# schematics.net
KiCad netlist of a schematic drawn in EAGLE
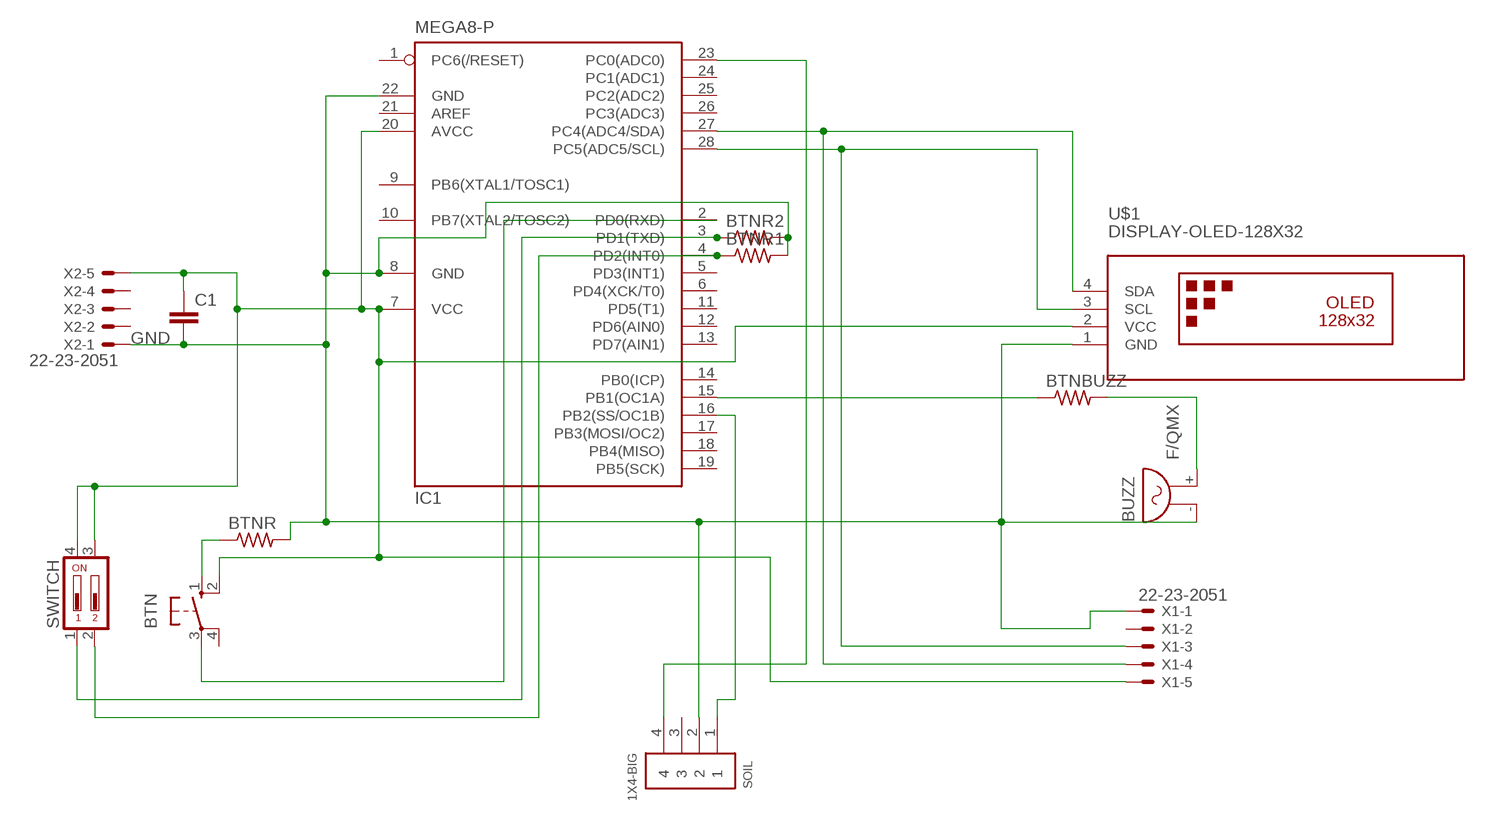
[diagram p0: schematic, sheet 1]

(export (version "E")
  (design (tool "Eeschema 10.0.6"))
  (components
    (comp (ref "BTN")
      (value "10-XX")
      (footprint "eagle-import:B3F-10XX")
      (fields (field (name "MPN") "B3F-1000"))
      (libsource (lib "eagle-import") (part "10-XX"))
    )
    (comp (ref "BTNBUZZ")
      (value "R-US_0204/7")
      (footprint "eagle-import:0204_7")
      (libsource (lib "eagle-import") (part "R-US_0204/7"))
    )
    (comp (ref "BTNR")
      (value "R-US_0204/7")
      (footprint "eagle-import:0204_7")
      (libsource (lib "eagle-import") (part "R-US_0204/7"))
    )
    (comp (ref "BTNR1")
      (value "R-US_0204/7")
      (footprint "eagle-import:0204_7")
      (libsource (lib "eagle-import") (part "R-US_0204/7"))
    )
    (comp (ref "BTNR2")
      (value "R-US_0204/7")
      (footprint "eagle-import:0204_7")
      (libsource (lib "eagle-import") (part "R-US_0204/7"))
    )
    (comp (ref "BUZZ")
      (value "F/QMX")
      (footprint "eagle-import:F_QMX")
      (libsource (lib "eagle-import") (part "F/QMX"))
    )
    (comp (ref "C1")
      (value "C-EU025-025X050")
      (footprint "eagle-import:C025-025X050")
      (libsource (lib "eagle-import") (part "C-EU025-025X050"))
    )
    (comp (ref "IC1")
      (value "MEGA8-P")
      (footprint "eagle-import:DIL28-3")
      (libsource (lib "eagle-import") (part "MEGA8-P"))
    )
    (comp (ref "SOIL")
      (value "1X4-BIG")
      (footprint "eagle-import:1X04-BIG")
      (libsource (lib "eagle-import") (part "1X4-BIG"))
    )
    (comp (ref "SWITCH")
      (value "DIP02YL")
      (footprint "eagle-import:DIP02YL")
      (libsource (lib "eagle-import") (part "DIP02YL"))
    )
    (comp (ref "U$1")
      (value "DISPLAY-OLED-128X32")
      (footprint "eagle-import:DISPLAY-OLED-128X32")
      (libsource (lib "eagle-import") (part "DISPLAY-OLED-128X32"))
    )
    (comp (ref "X1")
      (value "22-23-2051")
      (footprint "eagle-import:22-23-2051")
      (fields (field (name "MF") "MOLEX"))
      (libsource (lib "eagle-import") (part "22-23-2051"))
    )
    (comp (ref "X2")
      (value "22-23-2051")
      (footprint "eagle-import:22-23-2051")
      (fields (field (name "MF") "MOLEX"))
      (libsource (lib "eagle-import") (part "22-23-2051"))
    )
  )
  (nets
    (net (code "1") (name "/GND") (class "Default")
      (node (ref "BTNR") (pin "2") (pinfunction "2_2") (pintype "passive"))
      (node (ref "BTNR1") (pin "2") (pinfunction "2_2") (pintype "passive"))
      (node (ref "BTNR2") (pin "2") (pinfunction "2_2") (pintype "passive"))
      (node (ref "BUZZ") (pin "-") (pinfunction "1_-") (pintype "passive"))
      (node (ref "C1") (pin "2") (pinfunction "2_2") (pintype "passive"))
      (node (ref "IC1") (pin "22") (pinfunction "GND_22") (pintype "power_in"))
      (node (ref "IC1") (pin "8") (pinfunction "GND_8") (pintype "power_in"))
      (node (ref "SOIL") (pin "2") (pinfunction "2_2") (pintype "bidirectional"))
      (node (ref "U$1") (pin "1") (pinfunction "GND_1") (pintype "power_in"))
      (node (ref "X1") (pin "1") (pinfunction "S_1") (pintype "passive"))
      (node (ref "X2") (pin "1") (pinfunction "S_1") (pintype "passive"))
    )
    (net (code "2") (name "Net-(BTN-P)") (class "Default")
      (node (ref "BTN") (pin "3") (pinfunction "P_3") (pintype "passive"))
      (node (ref "IC1") (pin "2") (pinfunction "PD0(RXD)_2") (pintype "bidirectional"))
    )
    (net (code "3") (name "Net-(BTN-S)") (class "Default")
      (node (ref "BTN") (pin "1") (pinfunction "S_1") (pintype "passive"))
      (node (ref "BTNR") (pin "1") (pinfunction "1_1") (pintype "passive"))
    )
    (net (code "4") (name "Net-(BTN-S1)") (class "Default")
      (node (ref "BTN") (pin "2") (pinfunction "S1_2") (pintype "passive"))
      (node (ref "C1") (pin "1") (pinfunction "1_1") (pintype "passive"))
      (node (ref "IC1") (pin "20") (pinfunction "AVCC_20") (pintype "power_in"))
      (node (ref "IC1") (pin "7") (pinfunction "VCC_7") (pintype "power_in"))
      (node (ref "SWITCH") (pin "3") (pinfunction "3_3") (pintype "passive"))
      (node (ref "SWITCH") (pin "4") (pinfunction "4_4") (pintype "passive"))
      (node (ref "U$1") (pin "2") (pinfunction "VCC_2") (pintype "power_in"))
      (node (ref "X1") (pin "5") (pinfunction "S_5") (pintype "passive"))
      (node (ref "X2") (pin "5") (pinfunction "S_5") (pintype "passive"))
    )
    (net (code "5") (name "Net-(BUZZ-2)") (class "Default")
      (node (ref "BTNBUZZ") (pin "2") (pinfunction "2_2") (pintype "passive"))
      (node (ref "BUZZ") (pin "+") (pinfunction "2_+") (pintype "passive"))
    )
    (net (code "6") (name "Net-(IC1-PB1(OC1A))") (class "Default")
      (node (ref "BTNBUZZ") (pin "1") (pinfunction "1_1") (pintype "passive"))
      (node (ref "IC1") (pin "15") (pinfunction "PB1(OC1A)_15") (pintype "bidirectional"))
    )
    (net (code "7") (name "Net-(IC1-PB2(SS{slash}OC1B))") (class "Default")
      (node (ref "IC1") (pin "16") (pinfunction "PB2(SS/OC1B)_16") (pintype "bidirectional"))
      (node (ref "SOIL") (pin "1") (pinfunction "1_1") (pintype "bidirectional"))
    )
    (net (code "8") (name "Net-(IC1-PC0(ADC0))") (class "Default")
      (node (ref "IC1") (pin "23") (pinfunction "PC0(ADC0)_23") (pintype "bidirectional"))
      (node (ref "SOIL") (pin "4") (pinfunction "4_4") (pintype "bidirectional"))
    )
    (net (code "9") (name "Net-(IC1-PC4(ADC4{slash}SDA))") (class "Default")
      (node (ref "IC1") (pin "27") (pinfunction "PC4(ADC4/SDA)_27") (pintype "bidirectional"))
      (node (ref "U$1") (pin "4") (pinfunction "SDA_4") (pintype "bidirectional"))
      (node (ref "X1") (pin "4") (pinfunction "S_4") (pintype "passive"))
    )
    (net (code "10") (name "Net-(IC1-PC5(ADC5{slash}SCL))") (class "Default")
      (node (ref "IC1") (pin "28") (pinfunction "PC5(ADC5/SCL)_28") (pintype "bidirectional"))
      (node (ref "U$1") (pin "3") (pinfunction "SCL_3") (pintype "bidirectional"))
      (node (ref "X1") (pin "3") (pinfunction "S_3") (pintype "passive"))
    )
    (net (code "11") (name "Net-(IC1-PD1(TXD))") (class "Default")
      (node (ref "BTNR2") (pin "1") (pinfunction "1_1") (pintype "passive"))
      (node (ref "IC1") (pin "3") (pinfunction "PD1(TXD)_3") (pintype "bidirectional"))
      (node (ref "SWITCH") (pin "1") (pinfunction "1_1") (pintype "passive"))
    )
    (net (code "12") (name "Net-(IC1-PD2(INT0))") (class "Default")
      (node (ref "BTNR1") (pin "1") (pinfunction "1_1") (pintype "passive"))
      (node (ref "IC1") (pin "4") (pinfunction "PD2(INT0)_4") (pintype "bidirectional"))
      (node (ref "SWITCH") (pin "2") (pinfunction "2_2") (pintype "passive"))
    )
    (net (code "13") (name "unconnected-(BTN-P1-Pad4)") (class "Default")
      (node (ref "BTN") (pin "4") (pinfunction "P1_4") (pintype "passive"))
    )
    (net (code "14") (name "unconnected-(IC1-AREF-Pad21)") (class "Default")
      (node (ref "IC1") (pin "21") (pinfunction "AREF_21") (pintype "passive"))
    )
    (net (code "15") (name "unconnected-(IC1-PB0(ICP)-Pad14)") (class "Default")
      (node (ref "IC1") (pin "14") (pinfunction "PB0(ICP)_14") (pintype "bidirectional"))
    )
    (net (code "16") (name "unconnected-(IC1-PB3(MOSI{slash}OC2)-Pad17)") (class "Default")
      (node (ref "IC1") (pin "17") (pinfunction "PB3(MOSI/OC2)_17") (pintype "bidirectional"))
    )
    (net (code "17") (name "unconnected-(IC1-PB4(MISO)-Pad18)") (class "Default")
      (node (ref "IC1") (pin "18") (pinfunction "PB4(MISO)_18") (pintype "bidirectional"))
    )
    (net (code "18") (name "unconnected-(IC1-PB5(SCK)-Pad19)") (class "Default")
      (node (ref "IC1") (pin "19") (pinfunction "PB5(SCK)_19") (pintype "bidirectional"))
    )
    (net (code "19") (name "unconnected-(IC1-PB6(XTAL1{slash}TOSC1)-Pad9)") (class "Default")
      (node (ref "IC1") (pin "9") (pinfunction "PB6(XTAL1/TOSC1)_9") (pintype "bidirectional"))
    )
    (net (code "20") (name "unconnected-(IC1-PB7(XTAL2{slash}TOSC2)-Pad10)") (class "Default")
      (node (ref "IC1") (pin "10") (pinfunction "PB7(XTAL2/TOSC2)_10") (pintype "bidirectional"))
    )
    (net (code "21") (name "unconnected-(IC1-PC1(ADC1)-Pad24)") (class "Default")
      (node (ref "IC1") (pin "24") (pinfunction "PC1(ADC1)_24") (pintype "bidirectional"))
    )
    (net (code "22") (name "unconnected-(IC1-PC2(ADC2)-Pad25)") (class "Default")
      (node (ref "IC1") (pin "25") (pinfunction "PC2(ADC2)_25") (pintype "bidirectional"))
    )
    (net (code "23") (name "unconnected-(IC1-PC3(ADC3)-Pad26)") (class "Default")
      (node (ref "IC1") (pin "26") (pinfunction "PC3(ADC3)_26") (pintype "bidirectional"))
    )
    (net (code "24") (name "unconnected-(IC1-PC6({slash}RESET)-Pad1)") (class "Default")
      (node (ref "IC1") (pin "1") (pinfunction "PC6(/RESET)_1") (pintype "bidirectional"))
    )
    (net (code "25") (name "unconnected-(IC1-PD3(INT1)-Pad5)") (class "Default")
      (node (ref "IC1") (pin "5") (pinfunction "PD3(INT1)_5") (pintype "bidirectional"))
    )
    (net (code "26") (name "unconnected-(IC1-PD4(XCK{slash}T0)-Pad6)") (class "Default")
      (node (ref "IC1") (pin "6") (pinfunction "PD4(XCK/T0)_6") (pintype "bidirectional"))
    )
    (net (code "27") (name "unconnected-(IC1-PD5(T1)-Pad11)") (class "Default")
      (node (ref "IC1") (pin "11") (pinfunction "PD5(T1)_11") (pintype "bidirectional"))
    )
    (net (code "28") (name "unconnected-(IC1-PD6(AIN0)-Pad12)") (class "Default")
      (node (ref "IC1") (pin "12") (pinfunction "PD6(AIN0)_12") (pintype "bidirectional"))
    )
    (net (code "29") (name "unconnected-(IC1-PD7(AIN1)-Pad13)") (class "Default")
      (node (ref "IC1") (pin "13") (pinfunction "PD7(AIN1)_13") (pintype "bidirectional"))
    )
    (net (code "30") (name "unconnected-(SOIL-Pad3)") (class "Default")
      (node (ref "SOIL") (pin "3") (pinfunction "3_3") (pintype "bidirectional"))
    )
    (net (code "31") (name "unconnected-(X1B-S-Pad2)") (class "Default")
      (node (ref "X1") (pin "2") (pinfunction "S_2") (pintype "passive"))
    )
    (net (code "32") (name "unconnected-(X2B-S-Pad2)") (class "Default")
      (node (ref "X2") (pin "2") (pinfunction "S_2") (pintype "passive"))
    )
    (net (code "33") (name "unconnected-(X2C-S-Pad3)") (class "Default")
      (node (ref "X2") (pin "3") (pinfunction "S_3") (pintype "passive"))
    )
    (net (code "34") (name "unconnected-(X2D-S-Pad4)") (class "Default")
      (node (ref "X2") (pin "4") (pinfunction "S_4") (pintype "passive"))
    )
  )
)
